# lineFollower.net
KiCad netlist of a schematic drawn in EAGLE
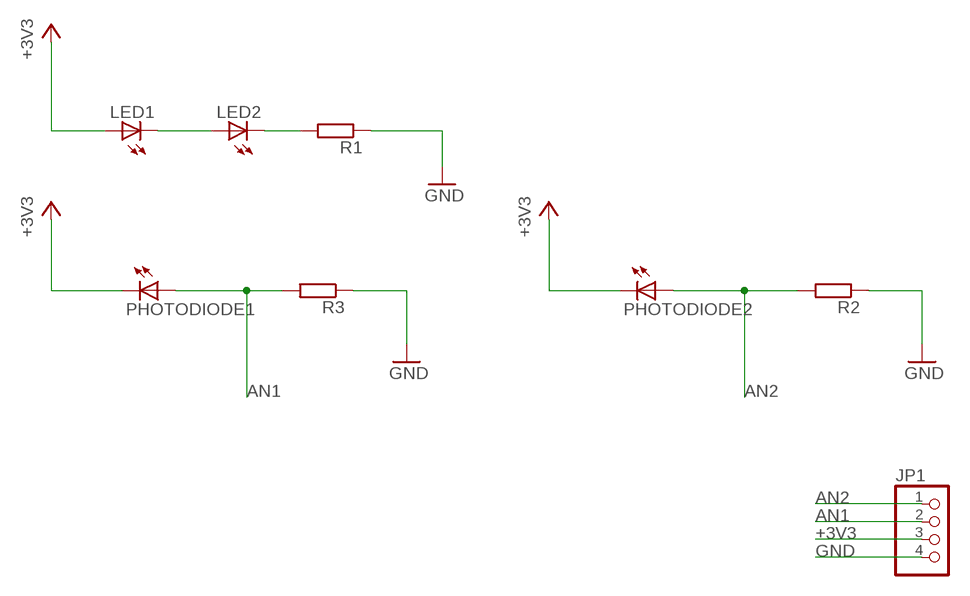
[diagram p0: schematic, sheet 1]

(export (version "E")
  (design (tool "Eeschema 10.0.6"))
  (components
    (comp (ref "JP1")
      (value "PINHD-1X4")
      (footprint "eagle-import:1X04")
      (libsource (lib "eagle-import") (part "PINHD-1X4"))
    )
    (comp (ref "LED1")
      (value "LED")
      (footprint "eagle-import:LED3MM_NARROW")
      (libsource (lib "eagle-import") (part "LED"))
    )
    (comp (ref "LED2")
      (value "LED")
      (footprint "eagle-import:LED3MM_NARROW")
      (libsource (lib "eagle-import") (part "LED"))
    )
    (comp (ref "PHOTODIODE1")
      (value "LED")
      (footprint "eagle-import:LED3MM_NARROW")
      (libsource (lib "eagle-import") (part "LED"))
    )
    (comp (ref "PHOTODIODE2")
      (value "LED")
      (footprint "eagle-import:LED3MM_NARROW")
      (libsource (lib "eagle-import") (part "LED"))
    )
    (comp (ref "R1")
      (value "R-EU_0204/5")
      (footprint "eagle-import:0204_5")
      (libsource (lib "eagle-import") (part "R-EU_0204/5"))
    )
    (comp (ref "R2")
      (value "R-EU_0204/5")
      (footprint "eagle-import:0204_5")
      (libsource (lib "eagle-import") (part "R-EU_0204/5"))
    )
    (comp (ref "R3")
      (value "R-EU_0204/5")
      (footprint "eagle-import:0204_5")
      (libsource (lib "eagle-import") (part "R-EU_0204/5"))
    )
  )
  (nets
    (net (code "1") (name "+3V3") (class "Default")
      (node (ref "JP1") (pin "3") (pinfunction "3_3") (pintype "passive"))
      (node (ref "LED1") (pin "A") (pinfunction "A_A") (pintype "passive"))
      (node (ref "PHOTODIODE1") (pin "K") (pinfunction "C_K") (pintype "passive"))
      (node (ref "PHOTODIODE2") (pin "K") (pinfunction "C_K") (pintype "passive"))
    )
    (net (code "2") (name "/AN1") (class "Default")
      (node (ref "JP1") (pin "2") (pinfunction "2_2") (pintype "passive"))
      (node (ref "PHOTODIODE1") (pin "A") (pinfunction "A_A") (pintype "passive"))
      (node (ref "R3") (pin "2") (pinfunction "2_2") (pintype "passive"))
    )
    (net (code "3") (name "/AN2") (class "Default")
      (node (ref "JP1") (pin "1") (pinfunction "1_1") (pintype "passive"))
      (node (ref "PHOTODIODE2") (pin "A") (pinfunction "A_A") (pintype "passive"))
      (node (ref "R2") (pin "2") (pinfunction "2_2") (pintype "passive"))
    )
    (net (code "4") (name "GND") (class "Default")
      (node (ref "JP1") (pin "4") (pinfunction "4_4") (pintype "passive"))
      (node (ref "R1") (pin "1") (pinfunction "1_1") (pintype "passive"))
      (node (ref "R2") (pin "1") (pinfunction "1_1") (pintype "passive"))
      (node (ref "R3") (pin "1") (pinfunction "1_1") (pintype "passive"))
    )
    (net (code "5") (name "Net-(LED1-C)") (class "Default")
      (node (ref "LED1") (pin "K") (pinfunction "C_K") (pintype "passive"))
      (node (ref "LED2") (pin "A") (pinfunction "A_A") (pintype "passive"))
    )
    (net (code "6") (name "Net-(LED2-C)") (class "Default")
      (node (ref "LED2") (pin "K") (pinfunction "C_K") (pintype "passive"))
      (node (ref "R1") (pin "2") (pinfunction "2_2") (pintype "passive"))
    )
  )
)
